# Schematic_1_2026-10-04.net
KiCad netlist of a schematic drawn in Altium Designer
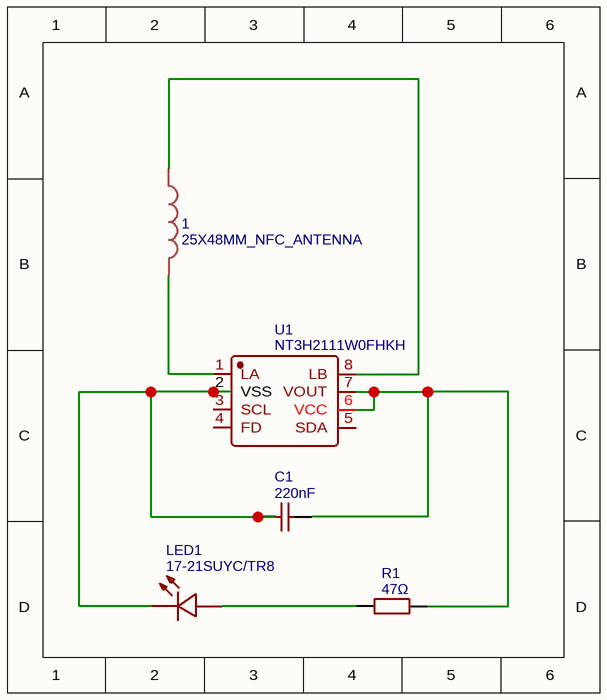
[diagram p0: Schematic_1_2026-10-04.schdoc]

(export (version "E")
  (design (tool "Eeschema 10.0.6"))
  (components
    (comp (ref "1")
      (value "25X48MM_NFC_ANTENNA")
      (fields (field (name "CONTRIBUTOR") "maggie.j.liu"))
      (libsource (lib "altium-import") (part "root_0_25X48MM_NFC_ANTENNA_"))
    )
    (comp (ref "C1")
      (value "220nF")
      (fields
        (field (name "MANUFACTURER PART") "CL10B224KA8NNNC")
        (field (name "MANUFACTURER") "SAMSUNG(三星)")
      )
      (libsource (lib "altium-import") (part "root_0_220nF_"))
    )
    (comp (ref "LED1")
      (value "17-21SUYC/TR8")
      (fields (field (name "MANUFACTURER") "KENTO") (field (name "MANUFACTURER PART") "KT-0805黄灯"))
      (libsource (lib "altium-import") (part "root_0_17-21SUYC/TR8_"))
    )
    (comp (ref "R1")
      (value "47Ω")
      (fields
        (field (name "MANUFACTURER") "UNI-ROYAL(厚声)")
        (field (name "MANUFACTURER PART") "0603WAF470JT5E")
      )
      (libsource (lib "altium-import") (part "root_0_47Ω_"))
    )
    (comp (ref "U1")
      (value "NT3H2111W0FHKH")
      (fields (field (name "MANUFACTURER") "NXP(恩智浦)") (field (name "CONTRIBUTOR") "LCSC"))
      (libsource (lib "altium-import") (part "root_0_NT3H2111W0FHKH_"))
    )
  )
  (nets
    (net (code "1") (name "Net-(LED1-+)") (class "Default")
      (node (ref "LED1") (pin "1") (pinfunction "+_1") (pintype "passive"))
      (node (ref "R1") (pin "1") (pinfunction "1_1") (pintype "passive"))
    )
    (net (code "2") (name "Net-(LED1--)") (class "Default")
      (node (ref "C1") (pin "1") (pinfunction "1_1") (pintype "passive"))
      (node (ref "LED1") (pin "2") (pinfunction "-_2") (pintype "passive"))
      (node (ref "U1") (pin "2") (pinfunction "VSS_2") (pintype "passive"))
    )
    (net (code "3") (name "Net-(U1-LA)") (class "Default")
      (node (ref "1") (pin "P$2") (pinfunction "P$2_P$2") (pintype "passive"))
      (node (ref "U1") (pin "1") (pinfunction "LA_1") (pintype "passive"))
    )
    (net (code "4") (name "Net-(U1-LB)") (class "Default")
      (node (ref "1") (pin "P$1") (pinfunction "P$1_P$1") (pintype "passive"))
      (node (ref "U1") (pin "8") (pinfunction "LB_8") (pintype "passive"))
    )
    (net (code "5") (name "Net-(U1-VCC)") (class "Default")
      (node (ref "C1") (pin "2") (pinfunction "2_2") (pintype "passive"))
      (node (ref "R1") (pin "2") (pinfunction "2_2") (pintype "passive"))
      (node (ref "U1") (pin "6") (pinfunction "VCC_6") (pintype "passive"))
      (node (ref "U1") (pin "7") (pinfunction "VOUT_7") (pintype "passive"))
    )
    (net (code "6") (name "unconnected-(U1-FD-Pad4)") (class "Default")
      (node (ref "U1") (pin "4") (pinfunction "FD_4") (pintype "passive"))
    )
    (net (code "7") (name "unconnected-(U1-SCL-Pad3)") (class "Default")
      (node (ref "U1") (pin "3") (pinfunction "SCL_3") (pintype "passive"))
    )
    (net (code "8") (name "unconnected-(U1-SDA-Pad5)") (class "Default")
      (node (ref "U1") (pin "5") (pinfunction "SDA_5") (pintype "passive"))
    )
  )
)
